# power_CTL.net
KiCad netlist of a schematic drawn in Altium Designer
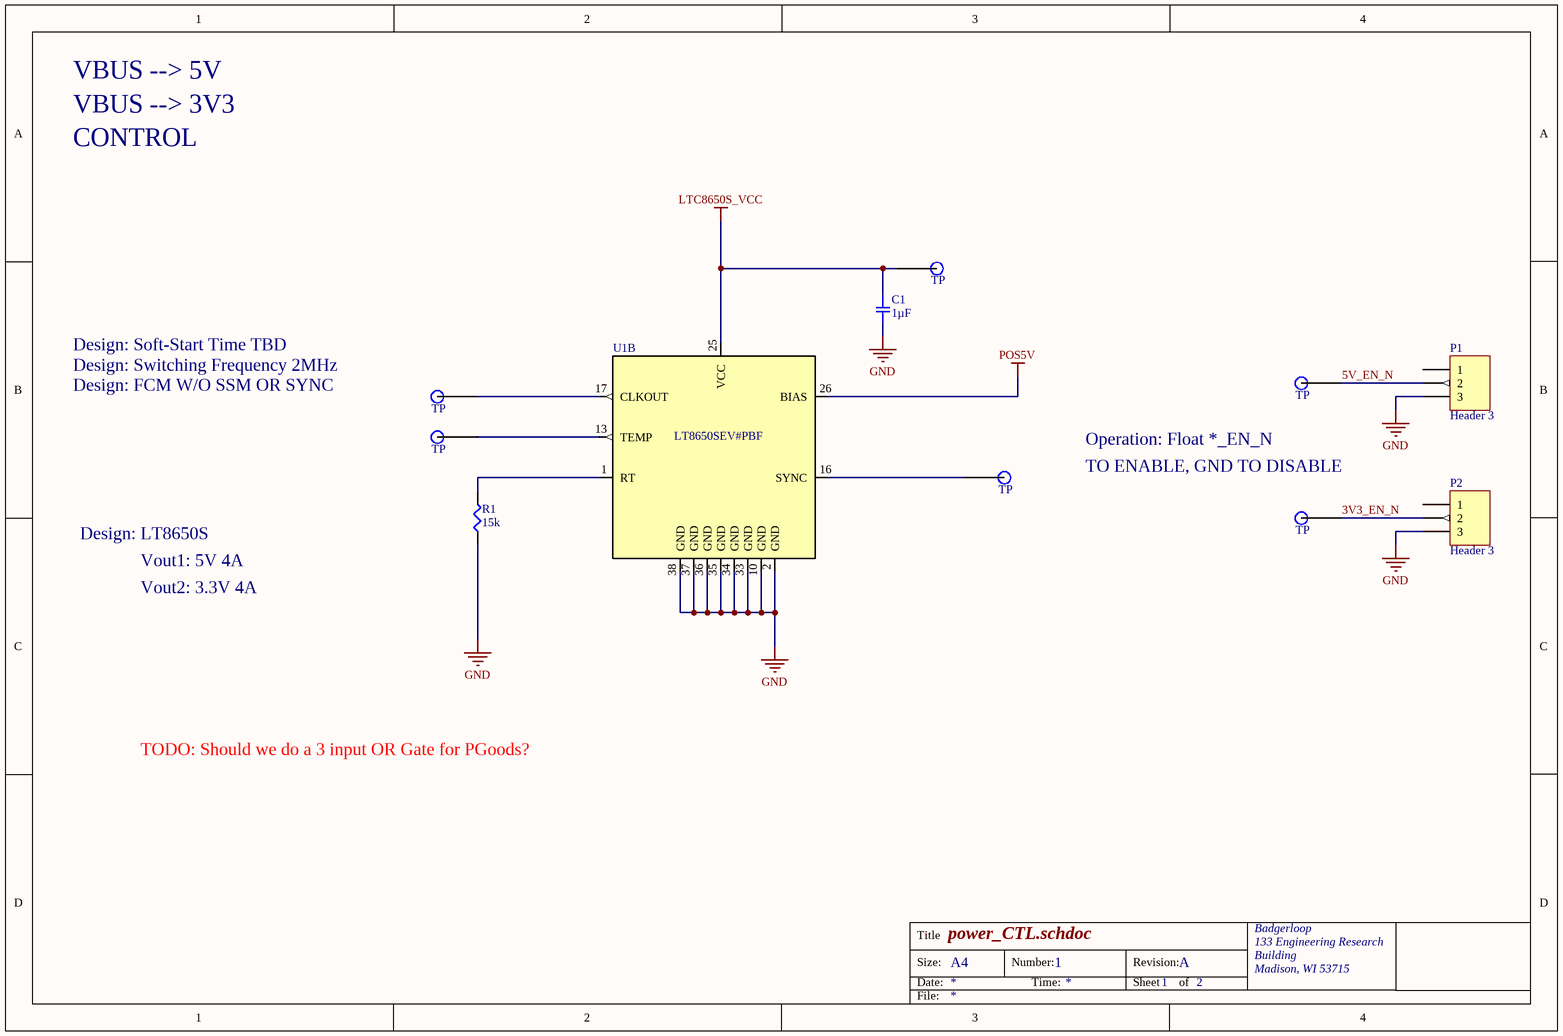
[diagram p0: power_CTL.schdoc]

(export (version "E")
  (design (tool "Eeschema 10.0.6"))
  (components
    (comp (ref "C1")
      (value "1µF")
      (footprint "SMD-0603C")
      (description "CAP CER 1UF 50V X5R 0603")
      (fields
        (field (name "DIGI-KEY PART NUMBER") "490-10732-1-ND")
        (field (name "PART NUMBER") "GRM188R61H105KAALD")
      )
      (libsource (lib "capacitor") (part "GRM188R61H105KAALD"))
    )
    (comp (ref "P1")
      (value "Header 3")
      (footprint "Pin Header 1x3 TH Pitch 2.54mm")
      (description "Header, 3-Pin")
      (fields (field (name "PUBLISHER") "Altium Limited"))
      (libsource (lib "connector") (part "Header 3"))
    )
    (comp (ref "P2")
      (value "Header 3")
      (footprint "Pin Header 1x3 TH Pitch 2.54mm")
      (description "Header, 3-Pin")
      (fields (field (name "PUBLISHER") "Altium Limited"))
      (libsource (lib "connector") (part "Header 3"))
    )
    (comp (ref "R1")
      (value "15k")
      (footprint "SMD-0402-RES")
      (description "RES SMD 15K OHM 5% 1/10W 0402")
      (fields (field (name "PART NUMBER") "ERJ-2GEJ153X") (field (name "DIGI-KEY PART NUMBER") "P15KJCT-ND"))
      (libsource (lib "resistor") (part "ERJ-2GEJ153X"))
    )
    (comp (ref "TP1") (value "TP") (footprint "Test Point") (libsource (lib "misc") (part "TP")))
    (comp (ref "TP2") (value "TP") (footprint "Test Point") (libsource (lib "misc") (part "TP")))
    (comp (ref "TP3") (value "TP") (footprint "Test Point") (libsource (lib "misc") (part "TP")))
    (comp (ref "TP4") (value "TP") (footprint "Test Point") (libsource (lib "misc") (part "TP")))
    (comp (ref "TP5") (value "TP") (footprint "Test Point") (libsource (lib "misc") (part "TP")))
    (comp (ref "TP6") (value "TP") (footprint "Test Point") (libsource (lib "misc") (part "TP")))
    (comp (ref "U1")
      (value "LT8650SEV#PBF")
      (footprint "QFN50P600X400X103-32N240X440")
      (fields
        (field (name "DIGI-KEY_PART_NUMBER") "LT8650SEV#PBF-ND")
        (field (name "MF") "Linear Technology")
      )
      (libsource (lib "ic") (part "LT8650SEV#PBF"))
    )
  )
  (nets
    (net (code "1") (name "/3V3_EN_N") (class "Default")
      (node (ref "P2") (pin "2") (pinfunction "2_2") (pintype "output"))
      (node (ref "TP6") (pin "1") (pinfunction "1_1") (pintype "passive"))
    )
    (net (code "2") (name "/5V_EN_N") (class "Default")
      (node (ref "P1") (pin "2") (pinfunction "2_2") (pintype "output"))
      (node (ref "TP2") (pin "1") (pinfunction "1_1") (pintype "passive"))
    )
    (net (code "3") (name "GND") (class "Default")
      (node (ref "C1") (pin "2") (pinfunction "2_2") (pintype "passive"))
      (node (ref "P1") (pin "3") (pinfunction "3_3") (pintype "passive"))
      (node (ref "P2") (pin "3") (pinfunction "3_3") (pintype "passive"))
      (node (ref "R1") (pin "1") (pinfunction "1_1") (pintype "passive"))
      (node (ref "U1") (pin "10") (pinfunction "GND_10") (pintype "passive"))
      (node (ref "U1") (pin "2") (pinfunction "GND_2") (pintype "passive"))
      (node (ref "U1") (pin "33") (pinfunction "GND_33") (pintype "passive"))
      (node (ref "U1") (pin "34") (pinfunction "GND_34") (pintype "passive"))
      (node (ref "U1") (pin "35") (pinfunction "GND_35") (pintype "passive"))
      (node (ref "U1") (pin "36") (pinfunction "GND_36") (pintype "passive"))
      (node (ref "U1") (pin "37") (pinfunction "GND_37") (pintype "passive"))
      (node (ref "U1") (pin "38") (pinfunction "GND_38") (pintype "passive"))
    )
    (net (code "4") (name "LTC8650S_VCC") (class "Default")
      (node (ref "C1") (pin "1") (pinfunction "1_1") (pintype "passive"))
      (node (ref "TP1") (pin "1") (pinfunction "1_1") (pintype "passive"))
      (node (ref "U1") (pin "25") (pinfunction "VCC_25") (pintype "passive"))
    )
    (net (code "5") (name "Net-(U1B-CLKOUT)") (class "Default")
      (node (ref "TP3") (pin "1") (pinfunction "1_1") (pintype "passive"))
      (node (ref "U1") (pin "17") (pinfunction "CLKOUT_17") (pintype "output"))
    )
    (net (code "6") (name "Net-(U1B-RT)") (class "Default")
      (node (ref "R1") (pin "2") (pinfunction "2_2") (pintype "passive"))
      (node (ref "U1") (pin "1") (pinfunction "RT_1") (pintype "passive"))
    )
    (net (code "7") (name "Net-(U1B-SYNC)") (class "Default")
      (node (ref "TP5") (pin "1") (pinfunction "1_1") (pintype "passive"))
      (node (ref "U1") (pin "16") (pinfunction "SYNC_16") (pintype "passive"))
    )
    (net (code "8") (name "Net-(U1B-TEMP)") (class "Default")
      (node (ref "TP4") (pin "1") (pinfunction "1_1") (pintype "passive"))
      (node (ref "U1") (pin "13") (pinfunction "TEMP_13") (pintype "output"))
    )
    (net (code "9") (name "POS5V") (class "Default")
      (node (ref "U1") (pin "26") (pinfunction "BIAS_26") (pintype "bidirectional"))
    )
    (net (code "10") (name "unconnected-(P1-Pad1)") (class "Default")
      (node (ref "P1") (pin "1") (pinfunction "1_1") (pintype "passive"))
    )
    (net (code "11") (name "unconnected-(P2-Pad1)") (class "Default")
      (node (ref "P2") (pin "1") (pinfunction "1_1") (pintype "passive"))
    )
  )
)
